# universky-POWER.net
KiCad netlist of a schematic drawn in Altium Designer
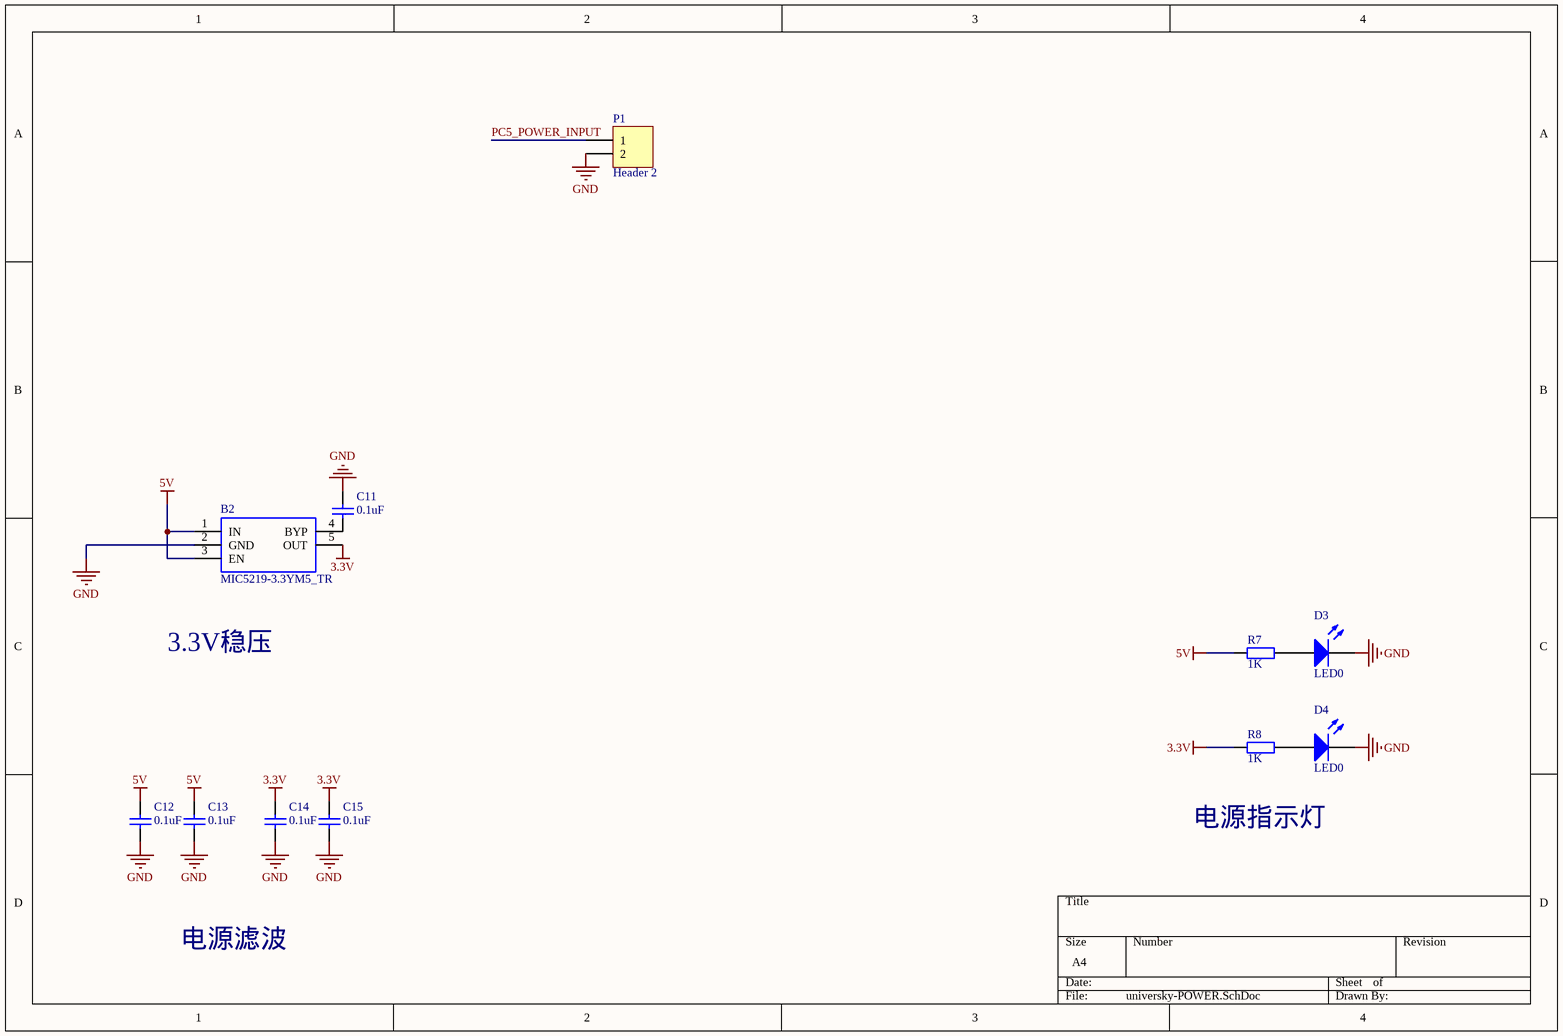
[diagram p0: universky-POWER.SchDoc]

(export (version "E")
  (design (tool "Eeschema 10.0.6"))
  (components
    (comp (ref "B2")
      (value "MIC5219-3.3YM5_TR")
      (footprint "SOT95P280X145-5N")
      (fields
        (field (name "RS PART NUMBER") "7272524")
        (field (name "MANUFACTURER_PART_NUMBER") "MIC5219-3.3YM5 TR")
      )
      (libsource (lib "universea") (part "MIC5219-3.3YM5_TR"))
    )
    (comp (ref "C11")
      (value "0.1uF")
      (footprint "0603_C")
      (description "Capacitor")
      (fields (field (name "Comment") "Cap") (field (name "PUBLISHER") "Altium Limited"))
      (libsource (lib "Miscellaneous Devices") (part "Cap"))
    )
    (comp (ref "C12")
      (value "0.1uF")
      (footprint "0603_C")
      (description "Capacitor")
      (fields (field (name "Comment") "Cap") (field (name "PUBLISHER") "Altium Limited"))
      (libsource (lib "Miscellaneous Devices") (part "Cap"))
    )
    (comp (ref "C13")
      (value "0.1uF")
      (footprint "0603_C")
      (description "Capacitor")
      (fields (field (name "Comment") "Cap") (field (name "PUBLISHER") "Altium Limited"))
      (libsource (lib "Miscellaneous Devices") (part "Cap"))
    )
    (comp (ref "C14")
      (value "0.1uF")
      (footprint "0603_C")
      (description "Capacitor")
      (fields (field (name "Comment") "Cap") (field (name "PUBLISHER") "Altium Limited"))
      (libsource (lib "Miscellaneous Devices") (part "Cap"))
    )
    (comp (ref "C15")
      (value "0.1uF")
      (footprint "0603_C")
      (description "Capacitor")
      (fields (field (name "Comment") "Cap") (field (name "PUBLISHER") "Altium Limited"))
      (libsource (lib "Miscellaneous Devices") (part "Cap"))
    )
    (comp (ref "D3")
      (value "LED0")
      (footprint "0603_LED")
      (description "Typical INFRARED GaAs LED")
      (fields (field (name "PUBLISHER") "Altium Limited"))
      (libsource (lib "Miscellaneous Devices") (part "LED0"))
    )
    (comp (ref "D4")
      (value "LED0")
      (footprint "0603_LED")
      (description "Typical INFRARED GaAs LED")
      (fields (field (name "PUBLISHER") "Altium Limited"))
      (libsource (lib "Miscellaneous Devices") (part "LED0"))
    )
    (comp (ref "P1")
      (value "Header 2")
      (footprint "HDR1X2")
      (description "Header, 2-Pin")
      (fields (field (name "PUBLISHER") "Altium Limited"))
      (libsource (lib "Miscellaneous Connectors") (part "Header 2"))
    )
    (comp (ref "R7")
      (value "1K")
      (footprint "0603_R")
      (description "Resistor")
      (fields (field (name "Comment") "Res2") (field (name "PUBLISHER") "Altium Limited"))
      (libsource (lib "Miscellaneous Devices") (part "Res2"))
    )
    (comp (ref "R8")
      (value "1K")
      (footprint "0603_R")
      (description "Resistor")
      (fields (field (name "Comment") "Res2") (field (name "PUBLISHER") "Altium Limited"))
      (libsource (lib "Miscellaneous Devices") (part "Res2"))
    )
  )
  (nets
    (net (code "1") (name "/PC5_POWER_INPUT") (class "Default")
      (node (ref "P1") (pin "1") (pinfunction "1_1") (pintype "passive"))
    )
    (net (code "2") (name "3.3V") (class "Default")
      (node (ref "B2") (pin "5") (pinfunction "OUT_5") (pintype "passive"))
      (node (ref "C14") (pin "2") (pinfunction "2_2") (pintype "passive"))
      (node (ref "C15") (pin "2") (pinfunction "2_2") (pintype "passive"))
      (node (ref "R8") (pin "1") (pinfunction "1_1") (pintype "passive"))
    )
    (net (code "3") (name "5V") (class "Default")
      (node (ref "B2") (pin "1") (pinfunction "IN_1") (pintype "passive"))
      (node (ref "B2") (pin "3") (pinfunction "EN_3") (pintype "passive"))
      (node (ref "C12") (pin "2") (pinfunction "2_2") (pintype "passive"))
      (node (ref "C13") (pin "2") (pinfunction "2_2") (pintype "passive"))
      (node (ref "R7") (pin "1") (pinfunction "1_1") (pintype "passive"))
    )
    (net (code "4") (name "GND") (class "Default")
      (node (ref "B2") (pin "2") (pinfunction "GND_2") (pintype "passive"))
      (node (ref "C11") (pin "2") (pinfunction "2_2") (pintype "passive"))
      (node (ref "C12") (pin "1") (pinfunction "1_1") (pintype "passive"))
      (node (ref "C13") (pin "1") (pinfunction "1_1") (pintype "passive"))
      (node (ref "C14") (pin "1") (pinfunction "1_1") (pintype "passive"))
      (node (ref "C15") (pin "1") (pinfunction "1_1") (pintype "passive"))
      (node (ref "D3") (pin "2") (pinfunction "K_2") (pintype "passive"))
      (node (ref "D4") (pin "2") (pinfunction "K_2") (pintype "passive"))
      (node (ref "P1") (pin "2") (pinfunction "2_2") (pintype "passive"))
    )
    (net (code "5") (name "Net-(B2-BYP)") (class "Default")
      (node (ref "B2") (pin "4") (pinfunction "BYP_4") (pintype "passive"))
      (node (ref "C11") (pin "1") (pinfunction "1_1") (pintype "passive"))
    )
    (net (code "6") (name "Net-(D3-A)") (class "Default")
      (node (ref "D3") (pin "1") (pinfunction "A_1") (pintype "passive"))
      (node (ref "R7") (pin "2") (pinfunction "2_2") (pintype "passive"))
    )
    (net (code "7") (name "Net-(D4-A)") (class "Default")
      (node (ref "D4") (pin "1") (pinfunction "A_1") (pintype "passive"))
      (node (ref "R8") (pin "2") (pinfunction "2_2") (pintype "passive"))
    )
  )
)
